# USB_OTG.net
KiCad netlist of a schematic drawn in Altium Designer
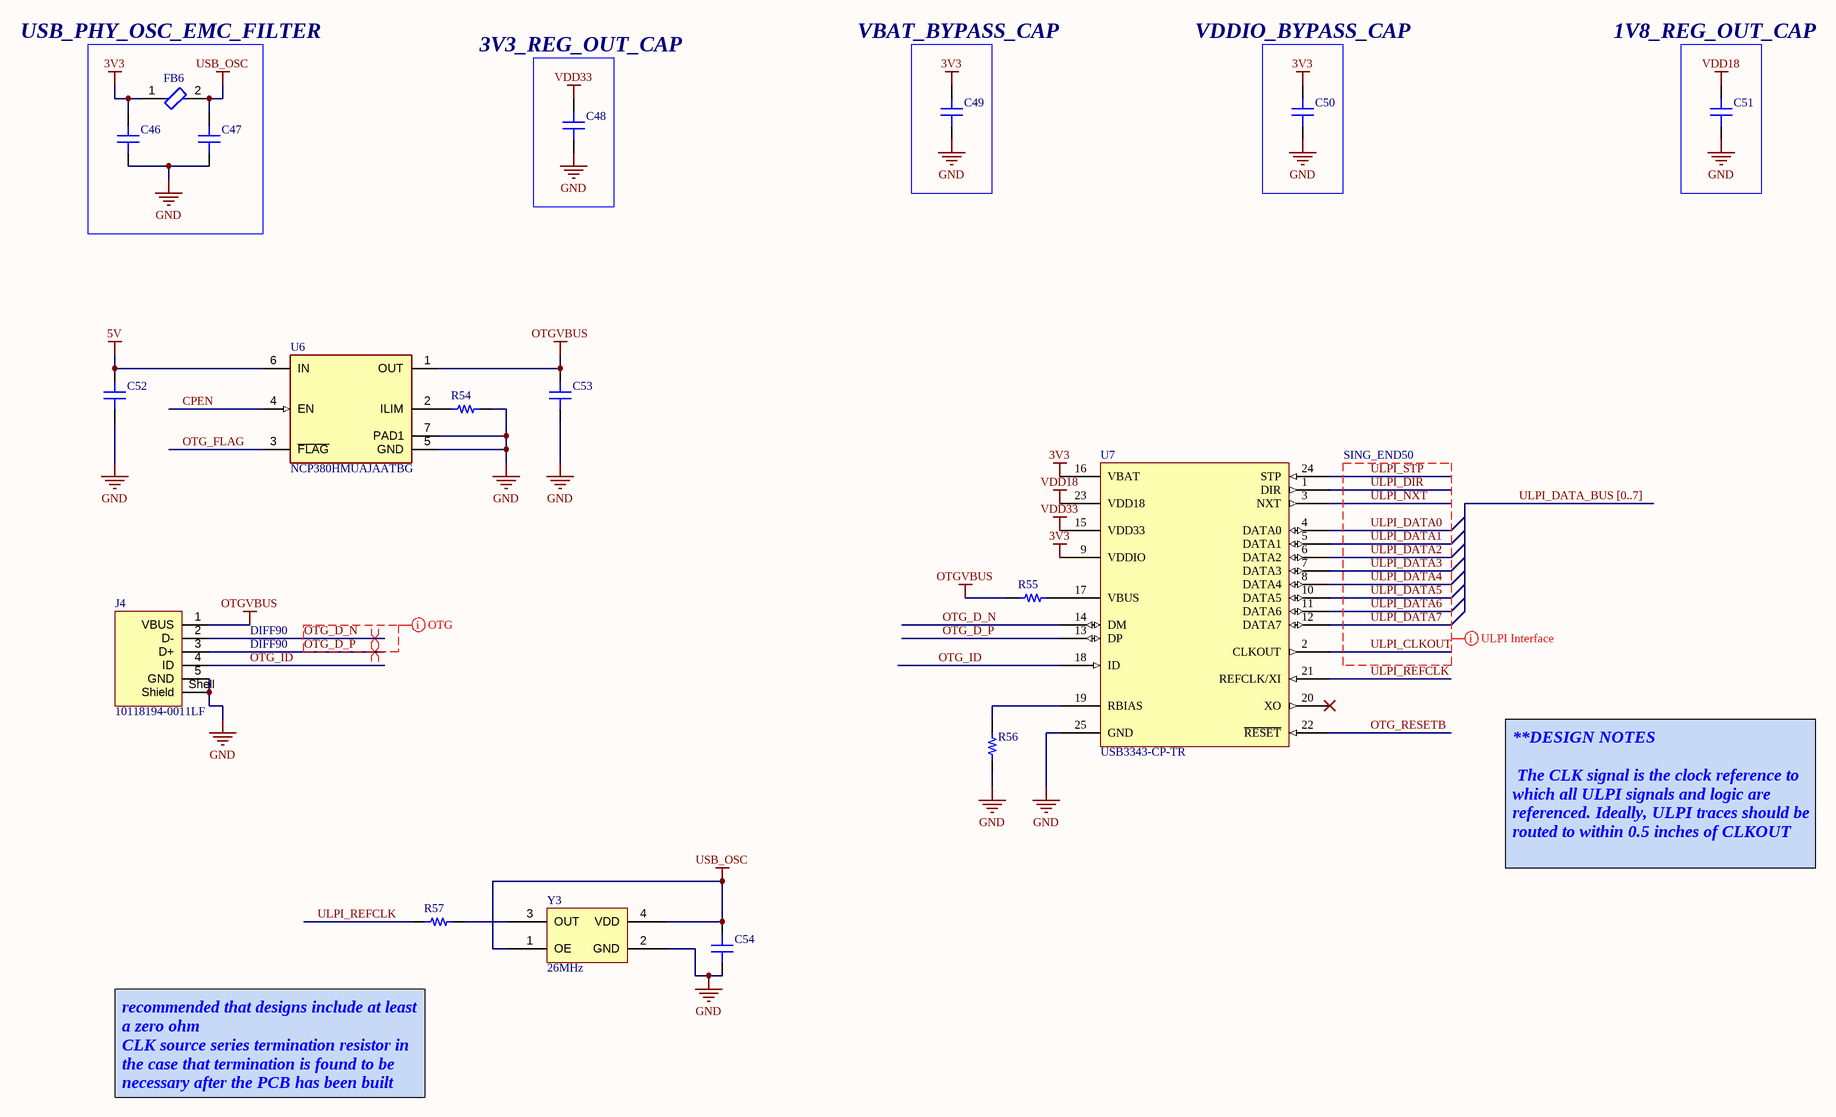
[diagram p0: USB_OTG.SchDoc]

(export (version "E")
  (design (tool "Eeschema 10.0.6"))
  (components
    (comp (ref "C46")
      (value "4.7 µF")
      (footprint "CAP 0402_1005")
      (description "CAP CER 4.7UF 10V X5R 0402")
      (fields
        (field (name "PART NUMBER") "CL05A475MP5NRNC")
        (field (name "MANUFACTURER") "Samsung Electro-Mechanics")
      )
      (libsource (lib "Celestial Altium Library - altium_library") (part "Capacitor"))
    )
    (comp (ref "C47")
      (value "4.7 µF")
      (footprint "CAP 0402_1005")
      (description "CAP CER 4.7UF 10V X5R 0402")
      (fields
        (field (name "PART NUMBER") "CL05A475MP5NRNC")
        (field (name "MANUFACTURER") "Samsung Electro-Mechanics")
      )
      (libsource (lib "Celestial Altium Library - altium_library") (part "Capacitor"))
    )
    (comp (ref "C48")
      (value "4.7µF")
      (footprint "CAP 0402_1005")
      (description "CAP CER 4.7UF 16V X5R 0402")
      (fields (field (name "PART NUMBER") "0402YD475MAT2A") (field (name "MANUFACTURER") "AVX Corporation"))
      (libsource (lib "Celestial Altium Library - altium_library") (part "Capacitor"))
    )
    (comp (ref "C49")
      (value "0.1 µF")
      (footprint "CAP 0402_1005")
      (description "CAP CER 0.1UF 10V X7R 0402")
      (fields (field (name "PART NUMBER") "CC0402KRX7R6BB104") (field (name "MANUFACTURER") "Yageo"))
      (libsource (lib "Celestial Altium Library - altium_library") (part "Capacitor"))
    )
    (comp (ref "C50")
      (value "0.1 µF")
      (footprint "CAP 0402_1005")
      (description "CAP CER 0.1UF 10V X7R 0402")
      (fields (field (name "PART NUMBER") "CC0402KRX7R6BB104") (field (name "MANUFACTURER") "Yageo"))
      (libsource (lib "Celestial Altium Library - altium_library") (part "Capacitor"))
    )
    (comp (ref "C51")
      (value "4.7µF")
      (footprint "CAP 0402_1005")
      (description "CAP CER 4.7UF 16V X5R 0402")
      (fields (field (name "PART NUMBER") "0402YD475MAT2A") (field (name "MANUFACTURER") "AVX Corporation"))
      (libsource (lib "Celestial Altium Library - altium_library") (part "Capacitor"))
    )
    (comp (ref "C52")
      (value "10 µF")
      (footprint "CAP 0402_1005")
      (description "CAP CER 10UF 10V X5R 0402")
      (fields
        (field (name "PART NUMBER") "CL05A106MP8NUB8")
        (field (name "MANUFACTURER") "Samsung Electro-Mechanics")
      )
      (libsource (lib "Celestial Altium Library - altium_library") (part "Capacitor"))
    )
    (comp (ref "C53")
      (value "4.7 µF")
      (footprint "CAP 1210_3225 - 1MM")
      (description "CAP CER 4.7UF 35V X5R 1210")
      (fields (field (name "PART NUMBER") "GMK325BJ475MN-T") (field (name "MANUFACTURER") "Taiyo Yuden"))
      (libsource (lib "Celestial Altium Library - altium_library") (part "Capacitor"))
    )
    (comp (ref "C54")
      (value "10000 pF")
      (footprint "CAP 0402_1005")
      (description "CAP CER 0402 10NF 50V X7R 10%")
      (fields (field (name "PART NUMBER") "C0402C103K5RECAUTO") (field (name "MANUFACTURER") "KEMET"))
      (libsource (lib "Celestial Altium Library - altium_library") (part "Capacitor"))
    )
    (comp (ref "FB6")
      (value "BLM15AX601SN1D")
      (footprint "FP-BLM15-0_05-IPC_B")
      (description "Chip Ferrite Bead, 0402, 600Ω @ 100MHz, 0.34Ω, 25%, 500mA")
      (fields (field (name "TOLERANCE") "25%"))
      (libsource (lib "Altium Content Vault") (part "5f30dd21d616792df468990f7003faa"))
    )
    (comp (ref "J4")
      (value "10118194-0011LF")
      (footprint "10118194-0011LF")
      (description "USB - micro B USB 2.0 Receptacle Connector 5 Position Surface Mount, Right Angle; Through Hole")
      (fields
        (field (name "DIGI-KEY PART NUMBER") "10118194-0011LF-ND")
        (field (name "MANUFACTURER") "Amphenol ICC (FCI)")
      )
      (libsource (lib "T8_devkit_PCB_1") (part "10118194-0011LF"))
    )
    (comp (ref "R54")
      (value "44.2 kOhms")
      (footprint "RES 0201_0603")
      (description "RES 44.2K OHM 1% 1/20W 0201")
      (fields (field (name "PART NUMBER") "RC0201FR-0744K2L") (field (name "MANUFACTURER") "Yageo"))
      (libsource (lib "Celestial Altium Library - altium_library") (part "Resistor"))
    )
    (comp (ref "R55")
      (value "20 kOhms")
      (footprint "RES 0201_0603")
      (description "RES 20K OHM 1% 1/20W 0201")
      (fields (field (name "PART NUMBER") "RC0201FR-0720KL") (field (name "MANUFACTURER") "Yageo"))
      (libsource (lib "Celestial Altium Library - altium_library") (part "Resistor"))
    )
    (comp (ref "R56")
      (value "8.06 kOhms")
      (footprint "RES 0201_0603")
      (description "RES 8.06K OHM 1% 1/20W 0201")
      (fields (field (name "PART NUMBER") "RC0201FR-078K06L") (field (name "MANUFACTURER") "Yageo"))
      (libsource (lib "Celestial Altium Library - altium_library") (part "Resistor"))
    )
    (comp (ref "R57")
      (value "0 Ohms")
      (footprint "RES 0201_0603")
      (description "RES 0 OHM JUMPER 1/20W 0201")
      (fields (field (name "PART NUMBER") "RC0201JR-070RL") (field (name "MANUFACTURER") "Yageo"))
      (libsource (lib "Celestial Altium Library - altium_library") (part "Resistor"))
    )
    (comp (ref "U6")
      (value "NCP380HMUAJAATBG")
      (footprint "FP-517AB-MFG")
      (description "IC PWR SWITCH P-CHAN 1:1 6UDFN")
      (fields
        (field (name "OCTOPART") "https://octopart.com/ncp380hmuajaatbg-on+semiconductor-19977070")
        (field (name "MANUFACTURER") "ON Semiconductor")
      )
      (libsource (lib "Altium Content Vault") (part "723a6d5456884fc28e5ecf41c24379e"))
    )
    (comp (ref "U7")
      (value "USB3343-CP-TR")
      (footprint "FP-C04-208-IPC_B")
      (description "Vqfn 26Mhz Usb 2.0 Ulpi Phy With Variable I/O Voltage Rohs Compliant: Yes")
      (libsource (lib "Kocaeli University") (part "cb63a571a9d57fbe4804022124e6cad"))
    )
    (comp (ref "Y3")
      (value "26MHz")
      (footprint "ABRACON ASVTX-11")
      (description "XTAL OSC VCTCXO 26.0000MHZ SNWV")
      (fields
        (field (name "PART NUMBER") "ASVTX-11-A-26.000MHZ-T")
        (field (name "MANUFACTURER") "Abracon LLC")
      )
      (libsource (lib "Celestial Altium Library - altium_library") (part "Abracon VCTCXO ASVTX-11"))
    )
  )
  (nets
    (net (code "1") (name "/CPEN") (class "Default")
      (node (ref "U6") (pin "4") (pinfunction "EN_4") (pintype "input"))
    )
    (net (code "2") (name "/OTG_D_N") (class "Default")
      (node (ref "J4") (pin "2") (pinfunction "D-_2") (pintype "passive"))
      (node (ref "U7") (pin "14") (pinfunction "DM_14") (pintype "bidirectional"))
    )
    (net (code "3") (name "/OTG_D_P") (class "Default")
      (node (ref "J4") (pin "3") (pinfunction "D+_3") (pintype "passive"))
      (node (ref "U7") (pin "13") (pinfunction "DP_13") (pintype "bidirectional"))
    )
    (net (code "4") (name "/OTG_FLAG") (class "Default")
      (node (ref "U6") (pin "3") (pinfunction "~{FLAG}_3") (pintype "open_collector"))
    )
    (net (code "5") (name "/OTG_ID") (class "Default")
      (node (ref "J4") (pin "4") (pinfunction "ID_4") (pintype "passive"))
      (node (ref "U7") (pin "18") (pinfunction "ID_18") (pintype "input"))
    )
    (net (code "6") (name "/OTG_RESETB") (class "Default")
      (node (ref "U7") (pin "22") (pinfunction "~{RESET}_22") (pintype "input"))
    )
    (net (code "7") (name "/ULPI_CLKOUT") (class "Default")
      (node (ref "U7") (pin "2") (pinfunction "CLKOUT_2") (pintype "output"))
    )
    (net (code "8") (name "/ULPI_DATA0") (class "Default")
      (node (ref "U7") (pin "4") (pinfunction "DATA0_4") (pintype "bidirectional"))
    )
    (net (code "9") (name "/ULPI_DATA1") (class "Default")
      (node (ref "U7") (pin "5") (pinfunction "DATA1_5") (pintype "bidirectional"))
    )
    (net (code "10") (name "/ULPI_DATA2") (class "Default")
      (node (ref "U7") (pin "6") (pinfunction "DATA2_6") (pintype "bidirectional"))
    )
    (net (code "11") (name "/ULPI_DATA3") (class "Default")
      (node (ref "U7") (pin "7") (pinfunction "DATA3_7") (pintype "bidirectional"))
    )
    (net (code "12") (name "/ULPI_DATA4") (class "Default")
      (node (ref "U7") (pin "8") (pinfunction "DATA4_8") (pintype "bidirectional"))
    )
    (net (code "13") (name "/ULPI_DATA5") (class "Default")
      (node (ref "U7") (pin "10") (pinfunction "DATA5_10") (pintype "bidirectional"))
    )
    (net (code "14") (name "/ULPI_DATA6") (class "Default")
      (node (ref "U7") (pin "11") (pinfunction "DATA6_11") (pintype "bidirectional"))
    )
    (net (code "15") (name "/ULPI_DATA7") (class "Default")
      (node (ref "U7") (pin "12") (pinfunction "DATA7_12") (pintype "bidirectional"))
    )
    (net (code "16") (name "/ULPI_DIR") (class "Default")
      (node (ref "U7") (pin "1") (pinfunction "DIR_1") (pintype "output"))
    )
    (net (code "17") (name "/ULPI_NXT") (class "Default")
      (node (ref "U7") (pin "3") (pinfunction "NXT_3") (pintype "output"))
    )
    (net (code "18") (name "/ULPI_REFCLK") (class "Default")
      (node (ref "R57") (pin "1") (pinfunction "1_1") (pintype "passive"))
      (node (ref "U7") (pin "21") (pinfunction "REFCLK/XI_21") (pintype "input"))
    )
    (net (code "19") (name "/ULPI_STP") (class "Default")
      (node (ref "U7") (pin "24") (pinfunction "STP_24") (pintype "input"))
    )
    (net (code "21") (name "3V3") (class "Default")
      (node (ref "C46") (pin "2") (pinfunction "2_2") (pintype "passive"))
      (node (ref "C49") (pin "2") (pinfunction "2_2") (pintype "passive"))
      (node (ref "C50") (pin "2") (pinfunction "2_2") (pintype "passive"))
      (node (ref "FB6") (pin "1") (pinfunction "1_1") (pintype "passive"))
      (node (ref "U7") (pin "16") (pinfunction "VBAT_16") (pintype "power_in"))
      (node (ref "U7") (pin "9") (pinfunction "VDDIO_9") (pintype "power_in"))
    )
    (net (code "22") (name "5V") (class "Default")
      (node (ref "C52") (pin "2") (pinfunction "2_2") (pintype "passive"))
      (node (ref "U6") (pin "6") (pinfunction "IN_6") (pintype "power_in"))
    )
    (net (code "23") (name "GND") (class "Default")
      (node (ref "C46") (pin "1") (pinfunction "1_1") (pintype "passive"))
      (node (ref "C47") (pin "1") (pinfunction "1_1") (pintype "passive"))
      (node (ref "C48") (pin "1") (pinfunction "1_1") (pintype "passive"))
      (node (ref "C49") (pin "1") (pinfunction "1_1") (pintype "passive"))
      (node (ref "C50") (pin "1") (pinfunction "1_1") (pintype "passive"))
      (node (ref "C51") (pin "1") (pinfunction "1_1") (pintype "passive"))
      (node (ref "C52") (pin "1") (pinfunction "1_1") (pintype "passive"))
      (node (ref "C53") (pin "1") (pinfunction "1_1") (pintype "passive"))
      (node (ref "C54") (pin "1") (pinfunction "1_1") (pintype "passive"))
      (node (ref "J4") (pin "5") (pinfunction "GND_5") (pintype "passive"))
      (node (ref "J4") (pin "Shell") (pinfunction "Shield_Shell") (pintype "passive"))
      (node (ref "R54") (pin "2") (pinfunction "2_2") (pintype "passive"))
      (node (ref "R56") (pin "1") (pinfunction "1_1") (pintype "passive"))
      (node (ref "U6") (pin "5") (pinfunction "GND_5") (pintype "power_in"))
      (node (ref "U6") (pin "7") (pinfunction "PAD1_7") (pintype "passive"))
      (node (ref "U7") (pin "25") (pinfunction "GND_25") (pintype "power_in"))
      (node (ref "Y3") (pin "2") (pinfunction "GND_2") (pintype "passive"))
    )
    (net (code "24") (name "Net-(U6-ILIM)") (class "Default")
      (node (ref "R54") (pin "1") (pinfunction "1_1") (pintype "passive"))
      (node (ref "U6") (pin "2") (pinfunction "ILIM_2") (pintype "passive"))
    )
    (net (code "25") (name "Net-(U7-RBIAS)") (class "Default")
      (node (ref "R56") (pin "2") (pinfunction "2_2") (pintype "passive"))
      (node (ref "U7") (pin "19") (pinfunction "RBIAS_19") (pintype "passive"))
    )
    (net (code "26") (name "Net-(U7-VBUS)") (class "Default")
      (node (ref "R55") (pin "2") (pinfunction "2_2") (pintype "passive"))
      (node (ref "U7") (pin "17") (pinfunction "VBUS_17") (pintype "power_in"))
    )
    (net (code "27") (name "Net-(Y3-OUT)") (class "Default")
      (node (ref "R57") (pin "2") (pinfunction "2_2") (pintype "passive"))
      (node (ref "Y3") (pin "3") (pinfunction "OUT_3") (pintype "passive"))
    )
    (net (code "28") (name "OTGVBUS") (class "Default")
      (node (ref "C53") (pin "2") (pinfunction "2_2") (pintype "passive"))
      (node (ref "J4") (pin "1") (pinfunction "VBUS_1") (pintype "passive"))
      (node (ref "R55") (pin "1") (pinfunction "1_1") (pintype "passive"))
      (node (ref "U6") (pin "1") (pinfunction "OUT_1") (pintype "power_in"))
    )
    (net (code "29") (name "USB_OSC") (class "Default")
      (node (ref "C47") (pin "2") (pinfunction "2_2") (pintype "passive"))
      (node (ref "C54") (pin "2") (pinfunction "2_2") (pintype "passive"))
      (node (ref "FB6") (pin "2") (pinfunction "2_2") (pintype "passive"))
      (node (ref "Y3") (pin "1") (pinfunction "OE_1") (pintype "passive"))
      (node (ref "Y3") (pin "4") (pinfunction "VDD_4") (pintype "passive"))
    )
    (net (code "30") (name "VDD18") (class "Default")
      (node (ref "C51") (pin "2") (pinfunction "2_2") (pintype "passive"))
      (node (ref "U7") (pin "23") (pinfunction "VDD18_23") (pintype "power_in"))
    )
    (net (code "31") (name "VDD33") (class "Default")
      (node (ref "C48") (pin "2") (pinfunction "2_2") (pintype "passive"))
      (node (ref "U7") (pin "15") (pinfunction "VDD33_15") (pintype "power_in"))
    )
    (net (code "32") (name "unconnected-(U7-XO-Pad20)") (class "Default")
      (node (ref "U7") (pin "20") (pinfunction "XO_20") (pintype "output+no_connect"))
    )
  )
)
